# mcu.net
KiCad netlist of a schematic drawn in Altium Designer
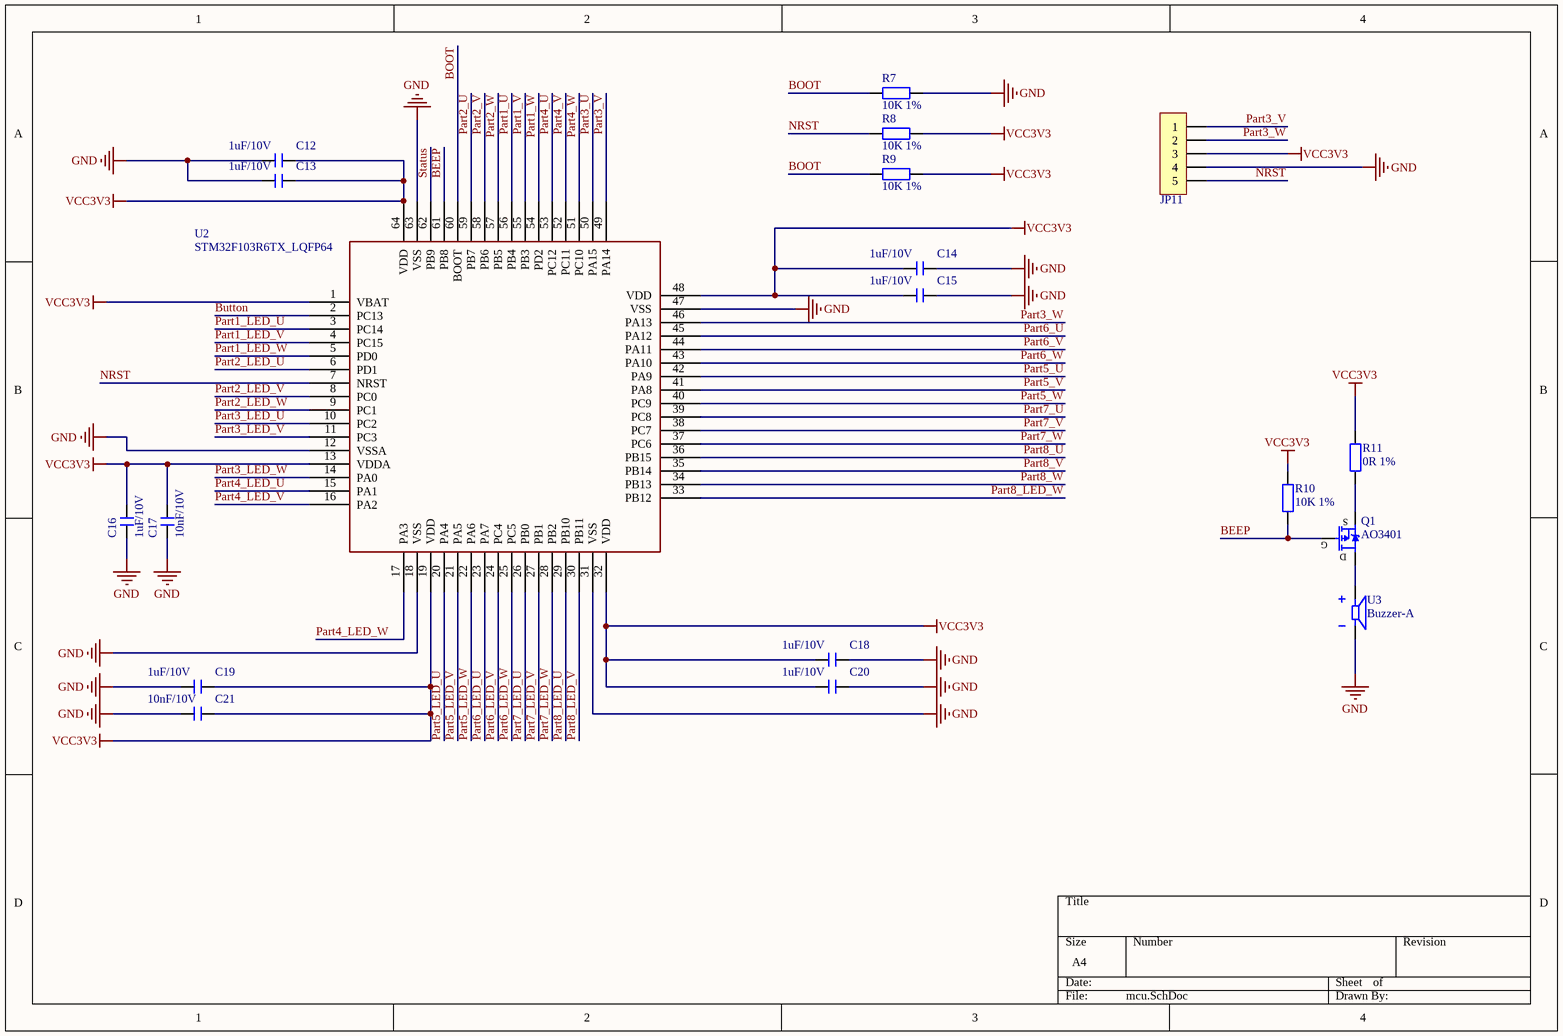
[diagram p0: mcu.SchDoc]

(export (version "E")
  (design (tool "Eeschema 10.0.6"))
  (components
    (comp (ref "C12")
      (value "1uF/10V")
      (footprint "C0603_L")
      (description "无极性贴片电容")
      (fields (field (name "版权归属") "源创客"))
      (libsource (lib "Capacitor") (part "C"))
    )
    (comp (ref "C13")
      (value "1uF/10V")
      (footprint "C0603_L")
      (description "无极性贴片电容")
      (fields (field (name "版权归属") "源创客"))
      (libsource (lib "Capacitor") (part "C"))
    )
    (comp (ref "C14")
      (value "1uF/10V")
      (footprint "C0603_L")
      (description "无极性贴片电容")
      (fields (field (name "版权归属") "源创客"))
      (libsource (lib "Capacitor") (part "C"))
    )
    (comp (ref "C15")
      (value "1uF/10V")
      (footprint "C0603_L")
      (description "无极性贴片电容")
      (fields (field (name "版权归属") "源创客"))
      (libsource (lib "Capacitor") (part "C"))
    )
    (comp (ref "C16")
      (value "1uF/10V")
      (footprint "C0603_L")
      (description "无极性贴片电容")
      (fields (field (name "版权归属") "源创客"))
      (libsource (lib "Capacitor") (part "C"))
    )
    (comp (ref "C17")
      (value "10nF/10V")
      (footprint "C0603_L")
      (description "无极性贴片电容")
      (fields (field (name "版权归属") "源创客"))
      (libsource (lib "Capacitor") (part "C"))
    )
    (comp (ref "C18")
      (value "1uF/10V")
      (footprint "C0603_L")
      (description "无极性贴片电容")
      (fields (field (name "版权归属") "源创客"))
      (libsource (lib "Capacitor") (part "C"))
    )
    (comp (ref "C19")
      (value "1uF/10V")
      (footprint "C0603_L")
      (description "无极性贴片电容")
      (fields (field (name "版权归属") "源创客"))
      (libsource (lib "Capacitor") (part "C"))
    )
    (comp (ref "C20")
      (value "1uF/10V")
      (footprint "C0603_L")
      (description "无极性贴片电容")
      (fields (field (name "版权归属") "源创客"))
      (libsource (lib "Capacitor") (part "C"))
    )
    (comp (ref "C21")
      (value "10nF/10V")
      (footprint "C0603_L")
      (description "无极性贴片电容")
      (fields (field (name "版权归属") "源创客"))
      (libsource (lib "Capacitor") (part "C"))
    )
    (comp (ref "JP11")
      (value "HDR-1X5")
      (footprint "HDR2.54-LI-5P")
      (description "5P接插件")
      (fields (field (name "版权归属") "源创客"))
      (libsource (lib "Connector-PinHeader") (part "Header 5"))
    )
    (comp (ref "Q1")
      (value "AO3401")
      (footprint "SOT23-3L")
      (description "P沟道 30V/4.2A")
      (fields (field (name "版权归属") "源创客"))
      (libsource (lib "MOSFET BJT IGBT") (part "AO3401"))
    )
    (comp (ref "R7")
      (value "10K 1%")
      (footprint "R0603_L")
      (description "贴片电阻")
      (fields (field (name "版权归属") "源创客"))
      (libsource (lib "Resistor") (part "R"))
    )
    (comp (ref "R8")
      (value "10K 1%")
      (footprint "R0603_L")
      (description "贴片电阻")
      (fields (field (name "版权归属") "源创客"))
      (libsource (lib "Resistor") (part "R"))
    )
    (comp (ref "R9")
      (value "10K 1%")
      (footprint "R0603_L")
      (description "贴片电阻")
      (fields (field (name "版权归属") "源创客"))
      (libsource (lib "Resistor") (part "R"))
    )
    (comp (ref "R10")
      (value "10K 1%")
      (footprint "R0603_L")
      (description "贴片电阻")
      (fields (field (name "版权归属") "源创客"))
      (libsource (lib "Resistor") (part "R"))
    )
    (comp (ref "R11")
      (value "0R 1%")
      (footprint "R0603_L")
      (description "贴片电阻")
      (fields (field (name "版权归属") "源创客"))
      (libsource (lib "Resistor") (part "R"))
    )
    (comp (ref "U2")
      (value "STM32F103R6TX_LQFP64")
      (footprint "LQFP64 10x10_N")
      (libsource (lib "MCU") (part "STM32F103R6TX_LQFP64"))
    )
    (comp (ref "U3")
      (value "Buzzer-A")
      (footprint "BEEP 5x9x5.5")
      (description "有源蜂鸣器")
      (libsource (lib "Others") (part "Buzzer-A"))
    )
  )
  (nets
    (net (code "1") (name "/BEEP") (class "Default")
      (node (ref "Q1") (pin "1") (pinfunction "G_1") (pintype "passive"))
      (node (ref "R10") (pin "1") (pinfunction "1_1") (pintype "passive"))
      (node (ref "U2") (pin "61") (pinfunction "PB8_61") (pintype "passive"))
    )
    (net (code "2") (name "/BOOT") (class "Default")
      (node (ref "R7") (pin "1") (pinfunction "1_1") (pintype "passive"))
      (node (ref "R9") (pin "1") (pinfunction "1_1") (pintype "passive"))
      (node (ref "U2") (pin "60") (pinfunction "BOOT_60") (pintype "passive"))
    )
    (net (code "3") (name "/Button") (class "Default")
      (node (ref "U2") (pin "2") (pinfunction "PC13_2") (pintype "passive"))
    )
    (net (code "4") (name "/NRST") (class "Default")
      (node (ref "JP11") (pin "5") (pinfunction "5_5") (pintype "passive"))
      (node (ref "R8") (pin "1") (pinfunction "1_1") (pintype "passive"))
      (node (ref "U2") (pin "7") (pinfunction "NRST_7") (pintype "passive"))
    )
    (net (code "5") (name "/Part1_LED_U") (class "Default")
      (node (ref "U2") (pin "3") (pinfunction "PC14_3") (pintype "passive"))
    )
    (net (code "6") (name "/Part1_LED_V") (class "Default")
      (node (ref "U2") (pin "4") (pinfunction "PC15_4") (pintype "passive"))
    )
    (net (code "7") (name "/Part1_LED_W") (class "Default")
      (node (ref "U2") (pin "5") (pinfunction "PD0_5") (pintype "passive"))
    )
    (net (code "8") (name "/Part1_U") (class "Default")
      (node (ref "U2") (pin "56") (pinfunction "PB4_56") (pintype "passive"))
    )
    (net (code "9") (name "/Part1_V") (class "Default")
      (node (ref "U2") (pin "55") (pinfunction "PB3_55") (pintype "passive"))
    )
    (net (code "10") (name "/Part1_W") (class "Default")
      (node (ref "U2") (pin "54") (pinfunction "PD2_54") (pintype "passive"))
    )
    (net (code "11") (name "/Part2_LED_U") (class "Default")
      (node (ref "U2") (pin "6") (pinfunction "PD1_6") (pintype "passive"))
    )
    (net (code "12") (name "/Part2_LED_V") (class "Default")
      (node (ref "U2") (pin "8") (pinfunction "PC0_8") (pintype "passive"))
    )
    (net (code "13") (name "/Part2_LED_W") (class "Default")
      (node (ref "U2") (pin "9") (pinfunction "PC1_9") (pintype "passive"))
    )
    (net (code "14") (name "/Part2_U") (class "Default")
      (node (ref "U2") (pin "59") (pinfunction "PB7_59") (pintype "passive"))
    )
    (net (code "15") (name "/Part2_V") (class "Default")
      (node (ref "U2") (pin "58") (pinfunction "PB6_58") (pintype "passive"))
    )
    (net (code "16") (name "/Part2_W") (class "Default")
      (node (ref "U2") (pin "57") (pinfunction "PB5_57") (pintype "passive"))
    )
    (net (code "17") (name "/Part3_LED_U") (class "Default")
      (node (ref "U2") (pin "10") (pinfunction "PC2_10") (pintype "passive"))
    )
    (net (code "18") (name "/Part3_LED_V") (class "Default")
      (node (ref "U2") (pin "11") (pinfunction "PC3_11") (pintype "passive"))
    )
    (net (code "19") (name "/Part3_LED_W") (class "Default")
      (node (ref "U2") (pin "14") (pinfunction "PA0_14") (pintype "passive"))
    )
    (net (code "20") (name "/Part3_U") (class "Default")
      (node (ref "U2") (pin "50") (pinfunction "PA15_50") (pintype "passive"))
    )
    (net (code "21") (name "/Part3_V") (class "Default")
      (node (ref "JP11") (pin "1") (pinfunction "1_1") (pintype "passive"))
      (node (ref "U2") (pin "49") (pinfunction "PA14_49") (pintype "passive"))
    )
    (net (code "22") (name "/Part3_W") (class "Default")
      (node (ref "JP11") (pin "2") (pinfunction "2_2") (pintype "passive"))
      (node (ref "U2") (pin "46") (pinfunction "PA13_46") (pintype "passive"))
    )
    (net (code "23") (name "/Part4_LED_U") (class "Default")
      (node (ref "U2") (pin "15") (pinfunction "PA1_15") (pintype "passive"))
    )
    (net (code "24") (name "/Part4_LED_V") (class "Default")
      (node (ref "U2") (pin "16") (pinfunction "PA2_16") (pintype "passive"))
    )
    (net (code "25") (name "/Part4_LED_W") (class "Default")
      (node (ref "U2") (pin "17") (pinfunction "PA3_17") (pintype "passive"))
    )
    (net (code "26") (name "/Part4_U") (class "Default")
      (node (ref "U2") (pin "53") (pinfunction "PC12_53") (pintype "passive"))
    )
    (net (code "27") (name "/Part4_V") (class "Default")
      (node (ref "U2") (pin "52") (pinfunction "PC11_52") (pintype "passive"))
    )
    (net (code "28") (name "/Part4_W") (class "Default")
      (node (ref "U2") (pin "51") (pinfunction "PC10_51") (pintype "passive"))
    )
    (net (code "29") (name "/Part5_LED_U") (class "Default")
      (node (ref "U2") (pin "20") (pinfunction "PA4_20") (pintype "passive"))
    )
    (net (code "30") (name "/Part5_LED_V") (class "Default")
      (node (ref "U2") (pin "21") (pinfunction "PA5_21") (pintype "passive"))
    )
    (net (code "31") (name "/Part5_LED_W") (class "Default")
      (node (ref "U2") (pin "22") (pinfunction "PA6_22") (pintype "passive"))
    )
    (net (code "32") (name "/Part5_U") (class "Default")
      (node (ref "U2") (pin "42") (pinfunction "PA9_42") (pintype "passive"))
    )
    (net (code "33") (name "/Part5_V") (class "Default")
      (node (ref "U2") (pin "41") (pinfunction "PA8_41") (pintype "passive"))
    )
    (net (code "34") (name "/Part5_W") (class "Default")
      (node (ref "U2") (pin "40") (pinfunction "PC9_40") (pintype "passive"))
    )
    (net (code "35") (name "/Part6_LED_U") (class "Default")
      (node (ref "U2") (pin "23") (pinfunction "PA7_23") (pintype "passive"))
    )
    (net (code "36") (name "/Part6_LED_V") (class "Default")
      (node (ref "U2") (pin "24") (pinfunction "PC4_24") (pintype "passive"))
    )
    (net (code "37") (name "/Part6_LED_W") (class "Default")
      (node (ref "U2") (pin "25") (pinfunction "PC5_25") (pintype "passive"))
    )
    (net (code "38") (name "/Part6_U") (class "Default")
      (node (ref "U2") (pin "45") (pinfunction "PA12_45") (pintype "passive"))
    )
    (net (code "39") (name "/Part6_V") (class "Default")
      (node (ref "U2") (pin "44") (pinfunction "PA11_44") (pintype "passive"))
    )
    (net (code "40") (name "/Part6_W") (class "Default")
      (node (ref "U2") (pin "43") (pinfunction "PA10_43") (pintype "passive"))
    )
    (net (code "41") (name "/Part7_LED_U") (class "Default")
      (node (ref "U2") (pin "26") (pinfunction "PB0_26") (pintype "passive"))
    )
    (net (code "42") (name "/Part7_LED_V") (class "Default")
      (node (ref "U2") (pin "27") (pinfunction "PB1_27") (pintype "passive"))
    )
    (net (code "43") (name "/Part7_LED_W") (class "Default")
      (node (ref "U2") (pin "28") (pinfunction "PB2_28") (pintype "passive"))
    )
    (net (code "44") (name "/Part7_U") (class "Default")
      (node (ref "U2") (pin "39") (pinfunction "PC8_39") (pintype "passive"))
    )
    (net (code "45") (name "/Part7_V") (class "Default")
      (node (ref "U2") (pin "38") (pinfunction "PC7_38") (pintype "passive"))
    )
    (net (code "46") (name "/Part7_W") (class "Default")
      (node (ref "U2") (pin "37") (pinfunction "PC6_37") (pintype "passive"))
    )
    (net (code "47") (name "/Part8_LED_U") (class "Default")
      (node (ref "U2") (pin "29") (pinfunction "PB10_29") (pintype "passive"))
    )
    (net (code "48") (name "/Part8_LED_V") (class "Default")
      (node (ref "U2") (pin "30") (pinfunction "PB11_30") (pintype "passive"))
    )
    (net (code "49") (name "/Part8_LED_W") (class "Default")
      (node (ref "U2") (pin "33") (pinfunction "PB12_33") (pintype "passive"))
    )
    (net (code "50") (name "/Part8_U") (class "Default")
      (node (ref "U2") (pin "36") (pinfunction "PB15_36") (pintype "passive"))
    )
    (net (code "51") (name "/Part8_V") (class "Default")
      (node (ref "U2") (pin "35") (pinfunction "PB14_35") (pintype "passive"))
    )
    (net (code "52") (name "/Part8_W") (class "Default")
      (node (ref "U2") (pin "34") (pinfunction "PB13_34") (pintype "passive"))
    )
    (net (code "53") (name "/Status") (class "Default")
      (node (ref "U2") (pin "62") (pinfunction "PB9_62") (pintype "passive"))
    )
    (net (code "54") (name "GND") (class "Default")
      (node (ref "C12") (pin "2") (pinfunction "2_2") (pintype "passive"))
      (node (ref "C13") (pin "2") (pinfunction "2_2") (pintype "passive"))
      (node (ref "C14") (pin "1") (pinfunction "1_1") (pintype "passive"))
      (node (ref "C15") (pin "1") (pinfunction "1_1") (pintype "passive"))
      (node (ref "C16") (pin "1") (pinfunction "1_1") (pintype "passive"))
      (node (ref "C17") (pin "1") (pinfunction "1_1") (pintype "passive"))
      (node (ref "C18") (pin "1") (pinfunction "1_1") (pintype "passive"))
      (node (ref "C19") (pin "2") (pinfunction "2_2") (pintype "passive"))
      (node (ref "C20") (pin "1") (pinfunction "1_1") (pintype "passive"))
      (node (ref "C21") (pin "2") (pinfunction "2_2") (pintype "passive"))
      (node (ref "JP11") (pin "4") (pinfunction "4_4") (pintype "passive"))
      (node (ref "R7") (pin "2") (pinfunction "2_2") (pintype "passive"))
      (node (ref "U2") (pin "12") (pinfunction "VSSA_12") (pintype "passive"))
      (node (ref "U2") (pin "18") (pinfunction "VSS_18") (pintype "passive"))
      (node (ref "U2") (pin "31") (pinfunction "VSS_31") (pintype "passive"))
      (node (ref "U2") (pin "47") (pinfunction "VSS_47") (pintype "passive"))
      (node (ref "U2") (pin "63") (pinfunction "VSS_63") (pintype "passive"))
      (node (ref "U3") (pin "2") (pinfunction "2_2") (pintype "passive"))
    )
    (net (code "55") (name "Net-(Q1-D)") (class "Default")
      (node (ref "Q1") (pin "3") (pinfunction "D_3") (pintype "passive"))
      (node (ref "U3") (pin "1") (pinfunction "1_1") (pintype "passive"))
    )
    (net (code "56") (name "Net-(Q1-S)") (class "Default")
      (node (ref "Q1") (pin "2") (pinfunction "S_2") (pintype "passive"))
      (node (ref "R11") (pin "1") (pinfunction "1_1") (pintype "passive"))
    )
    (net (code "57") (name "VCC3V3") (class "Default")
      (node (ref "C12") (pin "1") (pinfunction "1_1") (pintype "passive"))
      (node (ref "C13") (pin "1") (pinfunction "1_1") (pintype "passive"))
      (node (ref "C14") (pin "2") (pinfunction "2_2") (pintype "passive"))
      (node (ref "C15") (pin "2") (pinfunction "2_2") (pintype "passive"))
      (node (ref "C16") (pin "2") (pinfunction "2_2") (pintype "passive"))
      (node (ref "C17") (pin "2") (pinfunction "2_2") (pintype "passive"))
      (node (ref "C18") (pin "2") (pinfunction "2_2") (pintype "passive"))
      (node (ref "C19") (pin "1") (pinfunction "1_1") (pintype "passive"))
      (node (ref "C20") (pin "2") (pinfunction "2_2") (pintype "passive"))
      (node (ref "C21") (pin "1") (pinfunction "1_1") (pintype "passive"))
      (node (ref "JP11") (pin "3") (pinfunction "3_3") (pintype "passive"))
      (node (ref "R10") (pin "2") (pinfunction "2_2") (pintype "passive"))
      (node (ref "R11") (pin "2") (pinfunction "2_2") (pintype "passive"))
      (node (ref "R8") (pin "2") (pinfunction "2_2") (pintype "passive"))
      (node (ref "R9") (pin "2") (pinfunction "2_2") (pintype "passive"))
      (node (ref "U2") (pin "1") (pinfunction "VBAT_1") (pintype "passive"))
      (node (ref "U2") (pin "13") (pinfunction "VDDA_13") (pintype "passive"))
      (node (ref "U2") (pin "19") (pinfunction "VDD_19") (pintype "passive"))
      (node (ref "U2") (pin "32") (pinfunction "VDD_32") (pintype "passive"))
      (node (ref "U2") (pin "48") (pinfunction "VDD_48") (pintype "passive"))
      (node (ref "U2") (pin "64") (pinfunction "VDD_64") (pintype "passive"))
    )
  )
)
